# M050X.net
KiCad netlist of a schematic drawn in EAGLE
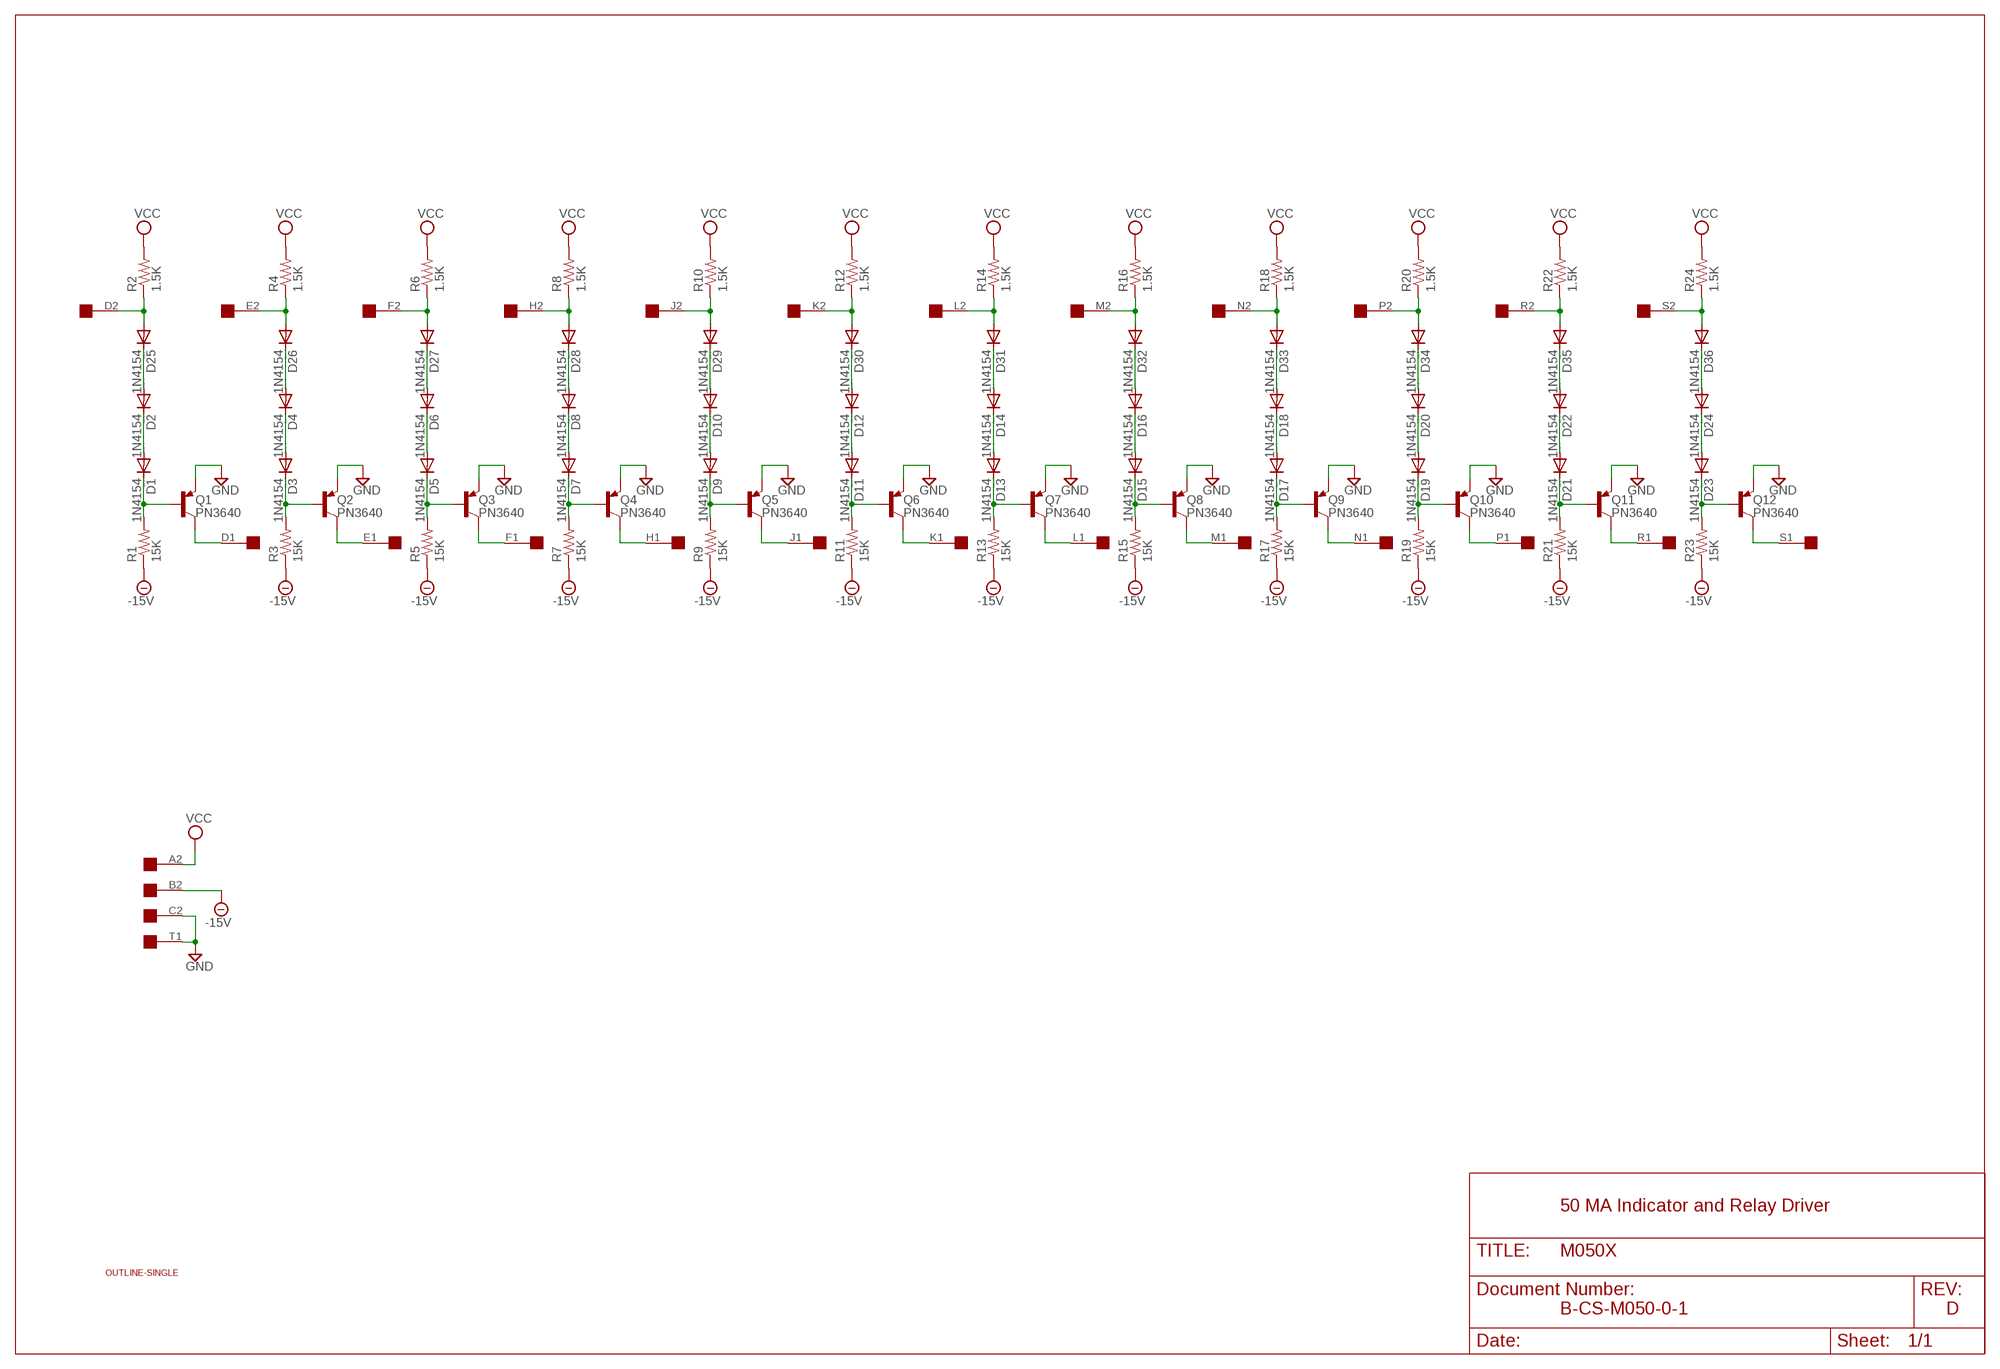
[diagram p0: schematic, sheet 1]

(export (version "E")
  (design (tool "Eeschema 10.0.6"))
  (components
    (comp (ref "D1")
      (value "1N4154")
      (footprint "eagle-import:DO35-10")
      (libsource (lib "eagle-import") (part "DIODE-DO35-10"))
    )
    (comp (ref "D2")
      (value "1N4154")
      (footprint "eagle-import:DO35-10")
      (libsource (lib "eagle-import") (part "DIODE-DO35-10"))
    )
    (comp (ref "D3")
      (value "1N4154")
      (footprint "eagle-import:DO35-10")
      (libsource (lib "eagle-import") (part "DIODE-DO35-10"))
    )
    (comp (ref "D4")
      (value "1N4154")
      (footprint "eagle-import:DO35-10")
      (libsource (lib "eagle-import") (part "DIODE-DO35-10"))
    )
    (comp (ref "D5")
      (value "1N4154")
      (footprint "eagle-import:DO35-10")
      (libsource (lib "eagle-import") (part "DIODE-DO35-10"))
    )
    (comp (ref "D6")
      (value "1N4154")
      (footprint "eagle-import:DO35-10")
      (libsource (lib "eagle-import") (part "DIODE-DO35-10"))
    )
    (comp (ref "D7")
      (value "1N4154")
      (footprint "eagle-import:DO35-10")
      (libsource (lib "eagle-import") (part "DIODE-DO35-10"))
    )
    (comp (ref "D8")
      (value "1N4154")
      (footprint "eagle-import:DO35-10")
      (libsource (lib "eagle-import") (part "DIODE-DO35-10"))
    )
    (comp (ref "D9")
      (value "1N4154")
      (footprint "eagle-import:DO35-10")
      (libsource (lib "eagle-import") (part "DIODE-DO35-10"))
    )
    (comp (ref "D10")
      (value "1N4154")
      (footprint "eagle-import:DO35-10")
      (libsource (lib "eagle-import") (part "DIODE-DO35-10"))
    )
    (comp (ref "D11")
      (value "1N4154")
      (footprint "eagle-import:DO35-10")
      (libsource (lib "eagle-import") (part "DIODE-DO35-10"))
    )
    (comp (ref "D12")
      (value "1N4154")
      (footprint "eagle-import:DO35-10")
      (libsource (lib "eagle-import") (part "DIODE-DO35-10"))
    )
    (comp (ref "D13")
      (value "1N4154")
      (footprint "eagle-import:DO35-10")
      (libsource (lib "eagle-import") (part "DIODE-DO35-10"))
    )
    (comp (ref "D14")
      (value "1N4154")
      (footprint "eagle-import:DO35-10")
      (libsource (lib "eagle-import") (part "DIODE-DO35-10"))
    )
    (comp (ref "D15")
      (value "1N4154")
      (footprint "eagle-import:DO35-10")
      (libsource (lib "eagle-import") (part "DIODE-DO35-10"))
    )
    (comp (ref "D16")
      (value "1N4154")
      (footprint "eagle-import:DO35-10")
      (libsource (lib "eagle-import") (part "DIODE-DO35-10"))
    )
    (comp (ref "D17")
      (value "1N4154")
      (footprint "eagle-import:DO35-10")
      (libsource (lib "eagle-import") (part "DIODE-DO35-10"))
    )
    (comp (ref "D18")
      (value "1N4154")
      (footprint "eagle-import:DO35-10")
      (libsource (lib "eagle-import") (part "DIODE-DO35-10"))
    )
    (comp (ref "D19")
      (value "1N4154")
      (footprint "eagle-import:DO35-10")
      (libsource (lib "eagle-import") (part "DIODE-DO35-10"))
    )
    (comp (ref "D20")
      (value "1N4154")
      (footprint "eagle-import:DO35-10")
      (libsource (lib "eagle-import") (part "DIODE-DO35-10"))
    )
    (comp (ref "D21")
      (value "1N4154")
      (footprint "eagle-import:DO35-10")
      (libsource (lib "eagle-import") (part "DIODE-DO35-10"))
    )
    (comp (ref "D22")
      (value "1N4154")
      (footprint "eagle-import:DO35-10")
      (libsource (lib "eagle-import") (part "DIODE-DO35-10"))
    )
    (comp (ref "D23")
      (value "1N4154")
      (footprint "eagle-import:DO35-10")
      (libsource (lib "eagle-import") (part "DIODE-DO35-10"))
    )
    (comp (ref "D24")
      (value "1N4154")
      (footprint "eagle-import:DO35-10")
      (libsource (lib "eagle-import") (part "DIODE-DO35-10"))
    )
    (comp (ref "D25")
      (value "1N4154")
      (footprint "eagle-import:DO35-10")
      (libsource (lib "eagle-import") (part "DIODE-DO35-10"))
    )
    (comp (ref "D26")
      (value "1N4154")
      (footprint "eagle-import:DO35-10")
      (libsource (lib "eagle-import") (part "DIODE-DO35-10"))
    )
    (comp (ref "D27")
      (value "1N4154")
      (footprint "eagle-import:DO35-10")
      (libsource (lib "eagle-import") (part "DIODE-DO35-10"))
    )
    (comp (ref "D28")
      (value "1N4154")
      (footprint "eagle-import:DO35-10")
      (libsource (lib "eagle-import") (part "DIODE-DO35-10"))
    )
    (comp (ref "D29")
      (value "1N4154")
      (footprint "eagle-import:DO35-10")
      (libsource (lib "eagle-import") (part "DIODE-DO35-10"))
    )
    (comp (ref "D30")
      (value "1N4154")
      (footprint "eagle-import:DO35-10")
      (libsource (lib "eagle-import") (part "DIODE-DO35-10"))
    )
    (comp (ref "D31")
      (value "1N4154")
      (footprint "eagle-import:DO35-10")
      (libsource (lib "eagle-import") (part "DIODE-DO35-10"))
    )
    (comp (ref "D32")
      (value "1N4154")
      (footprint "eagle-import:DO35-10")
      (libsource (lib "eagle-import") (part "DIODE-DO35-10"))
    )
    (comp (ref "D33")
      (value "1N4154")
      (footprint "eagle-import:DO35-10")
      (libsource (lib "eagle-import") (part "DIODE-DO35-10"))
    )
    (comp (ref "D34")
      (value "1N4154")
      (footprint "eagle-import:DO35-10")
      (libsource (lib "eagle-import") (part "DIODE-DO35-10"))
    )
    (comp (ref "D35")
      (value "1N4154")
      (footprint "eagle-import:DO35-10")
      (libsource (lib "eagle-import") (part "DIODE-DO35-10"))
    )
    (comp (ref "D36")
      (value "1N4154")
      (footprint "eagle-import:DO35-10")
      (libsource (lib "eagle-import") (part "DIODE-DO35-10"))
    )
    (comp (ref "Q1")
      (value "PN3640")
      (footprint "eagle-import:TO5")
      (libsource (lib "eagle-import") (part "-PNP-TO5"))
    )
    (comp (ref "Q2")
      (value "PN3640")
      (footprint "eagle-import:TO5")
      (libsource (lib "eagle-import") (part "-PNP-TO5"))
    )
    (comp (ref "Q3")
      (value "PN3640")
      (footprint "eagle-import:TO5")
      (libsource (lib "eagle-import") (part "-PNP-TO5"))
    )
    (comp (ref "Q4")
      (value "PN3640")
      (footprint "eagle-import:TO5")
      (libsource (lib "eagle-import") (part "-PNP-TO5"))
    )
    (comp (ref "Q5")
      (value "PN3640")
      (footprint "eagle-import:TO5")
      (libsource (lib "eagle-import") (part "-PNP-TO5"))
    )
    (comp (ref "Q6")
      (value "PN3640")
      (footprint "eagle-import:TO5")
      (libsource (lib "eagle-import") (part "-PNP-TO5"))
    )
    (comp (ref "Q7")
      (value "PN3640")
      (footprint "eagle-import:TO5")
      (libsource (lib "eagle-import") (part "-PNP-TO5"))
    )
    (comp (ref "Q8")
      (value "PN3640")
      (footprint "eagle-import:TO5")
      (libsource (lib "eagle-import") (part "-PNP-TO5"))
    )
    (comp (ref "Q9")
      (value "PN3640")
      (footprint "eagle-import:TO5")
      (libsource (lib "eagle-import") (part "-PNP-TO5"))
    )
    (comp (ref "Q10")
      (value "PN3640")
      (footprint "eagle-import:TO5")
      (libsource (lib "eagle-import") (part "-PNP-TO5"))
    )
    (comp (ref "Q11")
      (value "PN3640")
      (footprint "eagle-import:TO5")
      (libsource (lib "eagle-import") (part "-PNP-TO5"))
    )
    (comp (ref "Q12")
      (value "PN3640")
      (footprint "eagle-import:TO5")
      (libsource (lib "eagle-import") (part "-PNP-TO5"))
    )
    (comp (ref "R1")
      (value "15K")
      (footprint "eagle-import:0207_10")
      (libsource (lib "eagle-import") (part "R-US_0207/10"))
    )
    (comp (ref "R2")
      (value "1.5K")
      (footprint "eagle-import:0207_10")
      (libsource (lib "eagle-import") (part "R-US_0207/10"))
    )
    (comp (ref "R3")
      (value "15K")
      (footprint "eagle-import:0207_10")
      (libsource (lib "eagle-import") (part "R-US_0207/10"))
    )
    (comp (ref "R4")
      (value "1.5K")
      (footprint "eagle-import:0207_10")
      (libsource (lib "eagle-import") (part "R-US_0207/10"))
    )
    (comp (ref "R5")
      (value "15K")
      (footprint "eagle-import:0207_10")
      (libsource (lib "eagle-import") (part "R-US_0207/10"))
    )
    (comp (ref "R6")
      (value "1.5K")
      (footprint "eagle-import:0207_10")
      (libsource (lib "eagle-import") (part "R-US_0207/10"))
    )
    (comp (ref "R7")
      (value "15K")
      (footprint "eagle-import:0207_10")
      (libsource (lib "eagle-import") (part "R-US_0207/10"))
    )
    (comp (ref "R8")
      (value "1.5K")
      (footprint "eagle-import:0207_10")
      (libsource (lib "eagle-import") (part "R-US_0207/10"))
    )
    (comp (ref "R9")
      (value "15K")
      (footprint "eagle-import:0207_10")
      (libsource (lib "eagle-import") (part "R-US_0207/10"))
    )
    (comp (ref "R10")
      (value "1.5K")
      (footprint "eagle-import:0207_10")
      (libsource (lib "eagle-import") (part "R-US_0207/10"))
    )
    (comp (ref "R11")
      (value "15K")
      (footprint "eagle-import:0207_10")
      (libsource (lib "eagle-import") (part "R-US_0207/10"))
    )
    (comp (ref "R12")
      (value "1.5K")
      (footprint "eagle-import:0207_10")
      (libsource (lib "eagle-import") (part "R-US_0207/10"))
    )
    (comp (ref "R13")
      (value "15K")
      (footprint "eagle-import:0207_10")
      (libsource (lib "eagle-import") (part "R-US_0207/10"))
    )
    (comp (ref "R14")
      (value "1.5K")
      (footprint "eagle-import:0207_10")
      (libsource (lib "eagle-import") (part "R-US_0207/10"))
    )
    (comp (ref "R15")
      (value "15K")
      (footprint "eagle-import:0207_10")
      (libsource (lib "eagle-import") (part "R-US_0207/10"))
    )
    (comp (ref "R16")
      (value "1.5K")
      (footprint "eagle-import:0207_10")
      (libsource (lib "eagle-import") (part "R-US_0207/10"))
    )
    (comp (ref "R17")
      (value "15K")
      (footprint "eagle-import:0207_10")
      (libsource (lib "eagle-import") (part "R-US_0207/10"))
    )
    (comp (ref "R18")
      (value "1.5K")
      (footprint "eagle-import:0207_10")
      (libsource (lib "eagle-import") (part "R-US_0207/10"))
    )
    (comp (ref "R19")
      (value "15K")
      (footprint "eagle-import:0207_10")
      (libsource (lib "eagle-import") (part "R-US_0207/10"))
    )
    (comp (ref "R20")
      (value "1.5K")
      (footprint "eagle-import:0207_10")
      (libsource (lib "eagle-import") (part "R-US_0207/10"))
    )
    (comp (ref "R21")
      (value "15K")
      (footprint "eagle-import:0207_10")
      (libsource (lib "eagle-import") (part "R-US_0207/10"))
    )
    (comp (ref "R22")
      (value "1.5K")
      (footprint "eagle-import:0207_10")
      (libsource (lib "eagle-import") (part "R-US_0207/10"))
    )
    (comp (ref "R23")
      (value "15K")
      (footprint "eagle-import:0207_10")
      (libsource (lib "eagle-import") (part "R-US_0207/10"))
    )
    (comp (ref "R24")
      (value "1.5K")
      (footprint "eagle-import:0207_10")
      (libsource (lib "eagle-import") (part "R-US_0207/10"))
    )
    (comp (ref "U$1")
      (value "OUTLINE-SINGLE")
      (footprint "eagle-import:SINGLE")
      (libsource (lib "eagle-import") (part "OUTLINE-SINGLE"))
    )
    (comp (ref "U$2")
      (value "SINGLE")
      (footprint "eagle-import:EDGE-CON2")
      (libsource (lib "eagle-import") (part "SINGLE"))
    )
  )
  (nets
    (net (code "1") (name "-15V") (class "Default")
      (node (ref "R1") (pin "1") (pinfunction "1_1") (pintype "passive"))
      (node (ref "R11") (pin "1") (pinfunction "1_1") (pintype "passive"))
      (node (ref "R13") (pin "1") (pinfunction "1_1") (pintype "passive"))
      (node (ref "R15") (pin "1") (pinfunction "1_1") (pintype "passive"))
      (node (ref "R17") (pin "1") (pinfunction "1_1") (pintype "passive"))
      (node (ref "R19") (pin "1") (pinfunction "1_1") (pintype "passive"))
      (node (ref "R21") (pin "1") (pinfunction "1_1") (pintype "passive"))
      (node (ref "R23") (pin "1") (pinfunction "1_1") (pintype "passive"))
      (node (ref "R3") (pin "1") (pinfunction "1_1") (pintype "passive"))
      (node (ref "R5") (pin "1") (pinfunction "1_1") (pintype "passive"))
      (node (ref "R7") (pin "1") (pinfunction "1_1") (pintype "passive"))
      (node (ref "R9") (pin "1") (pinfunction "1_1") (pintype "passive"))
      (node (ref "U$2") (pin "B2") (pinfunction "1_B2") (pintype "bidirectional"))
    )
    (net (code "2") (name "GND") (class "Default")
      (node (ref "Q1") (pin "1") (pinfunction "E_1") (pintype "passive"))
      (node (ref "Q10") (pin "1") (pinfunction "E_1") (pintype "passive"))
      (node (ref "Q11") (pin "1") (pinfunction "E_1") (pintype "passive"))
      (node (ref "Q12") (pin "1") (pinfunction "E_1") (pintype "passive"))
      (node (ref "Q2") (pin "1") (pinfunction "E_1") (pintype "passive"))
      (node (ref "Q3") (pin "1") (pinfunction "E_1") (pintype "passive"))
      (node (ref "Q4") (pin "1") (pinfunction "E_1") (pintype "passive"))
      (node (ref "Q5") (pin "1") (pinfunction "E_1") (pintype "passive"))
      (node (ref "Q6") (pin "1") (pinfunction "E_1") (pintype "passive"))
      (node (ref "Q7") (pin "1") (pinfunction "E_1") (pintype "passive"))
      (node (ref "Q8") (pin "1") (pinfunction "E_1") (pintype "passive"))
      (node (ref "Q9") (pin "1") (pinfunction "E_1") (pintype "passive"))
      (node (ref "U$2") (pin "C2") (pinfunction "1_C2") (pintype "bidirectional"))
      (node (ref "U$2") (pin "T1") (pinfunction "1_T1") (pintype "bidirectional"))
    )
    (net (code "3") (name "Net-(D1-PadA)") (class "Default")
      (node (ref "D1") (pin "A") (pinfunction "A_A") (pintype "passive"))
      (node (ref "D2") (pin "C") (pinfunction "C_C") (pintype "passive"))
    )
    (net (code "4") (name "Net-(D2-PadA)") (class "Default")
      (node (ref "D2") (pin "A") (pinfunction "A_A") (pintype "passive"))
      (node (ref "D25") (pin "C") (pinfunction "C_C") (pintype "passive"))
    )
    (net (code "5") (name "Net-(D3-PadA)") (class "Default")
      (node (ref "D3") (pin "A") (pinfunction "A_A") (pintype "passive"))
      (node (ref "D4") (pin "C") (pinfunction "C_C") (pintype "passive"))
    )
    (net (code "6") (name "Net-(D5-PadA)") (class "Default")
      (node (ref "D5") (pin "A") (pinfunction "A_A") (pintype "passive"))
      (node (ref "D6") (pin "C") (pinfunction "C_C") (pintype "passive"))
    )
    (net (code "7") (name "Net-(D7-PadA)") (class "Default")
      (node (ref "D7") (pin "A") (pinfunction "A_A") (pintype "passive"))
      (node (ref "D8") (pin "C") (pinfunction "C_C") (pintype "passive"))
    )
    (net (code "8") (name "Net-(D10-PadA)") (class "Default")
      (node (ref "D10") (pin "A") (pinfunction "A_A") (pintype "passive"))
      (node (ref "D29") (pin "C") (pinfunction "C_C") (pintype "passive"))
    )
    (net (code "9") (name "Net-(D10-PadC)") (class "Default")
      (node (ref "D10") (pin "C") (pinfunction "C_C") (pintype "passive"))
      (node (ref "D9") (pin "A") (pinfunction "A_A") (pintype "passive"))
    )
    (net (code "10") (name "Net-(D11-PadA)") (class "Default")
      (node (ref "D11") (pin "A") (pinfunction "A_A") (pintype "passive"))
      (node (ref "D12") (pin "C") (pinfunction "C_C") (pintype "passive"))
    )
    (net (code "11") (name "Net-(D12-PadA)") (class "Default")
      (node (ref "D12") (pin "A") (pinfunction "A_A") (pintype "passive"))
      (node (ref "D30") (pin "C") (pinfunction "C_C") (pintype "passive"))
    )
    (net (code "12") (name "Net-(D13-PadA)") (class "Default")
      (node (ref "D13") (pin "A") (pinfunction "A_A") (pintype "passive"))
      (node (ref "D14") (pin "C") (pinfunction "C_C") (pintype "passive"))
    )
    (net (code "13") (name "Net-(D14-PadA)") (class "Default")
      (node (ref "D14") (pin "A") (pinfunction "A_A") (pintype "passive"))
      (node (ref "D31") (pin "C") (pinfunction "C_C") (pintype "passive"))
    )
    (net (code "14") (name "Net-(D15-PadA)") (class "Default")
      (node (ref "D15") (pin "A") (pinfunction "A_A") (pintype "passive"))
      (node (ref "D16") (pin "C") (pinfunction "C_C") (pintype "passive"))
    )
    (net (code "15") (name "Net-(D16-PadA)") (class "Default")
      (node (ref "D16") (pin "A") (pinfunction "A_A") (pintype "passive"))
      (node (ref "D32") (pin "C") (pinfunction "C_C") (pintype "passive"))
    )
    (net (code "16") (name "Net-(D17-PadA)") (class "Default")
      (node (ref "D17") (pin "A") (pinfunction "A_A") (pintype "passive"))
      (node (ref "D18") (pin "C") (pinfunction "C_C") (pintype "passive"))
    )
    (net (code "17") (name "Net-(D18-PadA)") (class "Default")
      (node (ref "D18") (pin "A") (pinfunction "A_A") (pintype "passive"))
      (node (ref "D33") (pin "C") (pinfunction "C_C") (pintype "passive"))
    )
    (net (code "18") (name "Net-(D19-PadA)") (class "Default")
      (node (ref "D19") (pin "A") (pinfunction "A_A") (pintype "passive"))
      (node (ref "D20") (pin "C") (pinfunction "C_C") (pintype "passive"))
    )
    (net (code "19") (name "Net-(D20-PadA)") (class "Default")
      (node (ref "D20") (pin "A") (pinfunction "A_A") (pintype "passive"))
      (node (ref "D34") (pin "C") (pinfunction "C_C") (pintype "passive"))
    )
    (net (code "20") (name "Net-(D21-PadA)") (class "Default")
      (node (ref "D21") (pin "A") (pinfunction "A_A") (pintype "passive"))
      (node (ref "D22") (pin "C") (pinfunction "C_C") (pintype "passive"))
    )
    (net (code "21") (name "Net-(D22-PadA)") (class "Default")
      (node (ref "D22") (pin "A") (pinfunction "A_A") (pintype "passive"))
      (node (ref "D35") (pin "C") (pinfunction "C_C") (pintype "passive"))
    )
    (net (code "22") (name "Net-(D23-PadA)") (class "Default")
      (node (ref "D23") (pin "A") (pinfunction "A_A") (pintype "passive"))
      (node (ref "D24") (pin "C") (pinfunction "C_C") (pintype "passive"))
    )
    (net (code "23") (name "Net-(D24-PadA)") (class "Default")
      (node (ref "D24") (pin "A") (pinfunction "A_A") (pintype "passive"))
      (node (ref "D36") (pin "C") (pinfunction "C_C") (pintype "passive"))
    )
    (net (code "24") (name "Net-(D26-PadC)") (class "Default")
      (node (ref "D26") (pin "C") (pinfunction "C_C") (pintype "passive"))
      (node (ref "D4") (pin "A") (pinfunction "A_A") (pintype "passive"))
    )
    (net (code "25") (name "Net-(D27-PadC)") (class "Default")
      (node (ref "D27") (pin "C") (pinfunction "C_C") (pintype "passive"))
      (node (ref "D6") (pin "A") (pinfunction "A_A") (pintype "passive"))
    )
    (net (code "26") (name "Net-(D28-PadC)") (class "Default")
      (node (ref "D28") (pin "C") (pinfunction "C_C") (pintype "passive"))
      (node (ref "D8") (pin "A") (pinfunction "A_A") (pintype "passive"))
    )
    (net (code "27") (name "Net-(Q1-B)") (class "Default")
      (node (ref "D1") (pin "C") (pinfunction "C_C") (pintype "passive"))
      (node (ref "Q1") (pin "2") (pinfunction "B_2") (pintype "passive"))
      (node (ref "R1") (pin "2") (pinfunction "2_2") (pintype "passive"))
    )
    (net (code "28") (name "Net-(Q1-C)") (class "Default")
      (node (ref "Q1") (pin "3") (pinfunction "C_3") (pintype "passive"))
      (node (ref "U$2") (pin "D1") (pinfunction "1_D1") (pintype "bidirectional"))
    )
    (net (code "29") (name "Net-(Q2-B)") (class "Default")
      (node (ref "D3") (pin "C") (pinfunction "C_C") (pintype "passive"))
      (node (ref "Q2") (pin "2") (pinfunction "B_2") (pintype "passive"))
      (node (ref "R3") (pin "2") (pinfunction "2_2") (pintype "passive"))
    )
    (net (code "30") (name "Net-(Q2-C)") (class "Default")
      (node (ref "Q2") (pin "3") (pinfunction "C_3") (pintype "passive"))
      (node (ref "U$2") (pin "E1") (pinfunction "1_E1") (pintype "bidirectional"))
    )
    (net (code "31") (name "Net-(Q3-B)") (class "Default")
      (node (ref "D5") (pin "C") (pinfunction "C_C") (pintype "passive"))
      (node (ref "Q3") (pin "2") (pinfunction "B_2") (pintype "passive"))
      (node (ref "R5") (pin "2") (pinfunction "2_2") (pintype "passive"))
    )
    (net (code "32") (name "Net-(Q3-C)") (class "Default")
      (node (ref "Q3") (pin "3") (pinfunction "C_3") (pintype "passive"))
      (node (ref "U$2") (pin "F1") (pinfunction "1_F1") (pintype "bidirectional"))
    )
    (net (code "33") (name "Net-(Q4-B)") (class "Default")
      (node (ref "D7") (pin "C") (pinfunction "C_C") (pintype "passive"))
      (node (ref "Q4") (pin "2") (pinfunction "B_2") (pintype "passive"))
      (node (ref "R7") (pin "2") (pinfunction "2_2") (pintype "passive"))
    )
    (net (code "34") (name "Net-(Q4-C)") (class "Default")
      (node (ref "Q4") (pin "3") (pinfunction "C_3") (pintype "passive"))
      (node (ref "U$2") (pin "H1") (pinfunction "1_H1") (pintype "bidirectional"))
    )
    (net (code "35") (name "Net-(Q5-B)") (class "Default")
      (node (ref "D9") (pin "C") (pinfunction "C_C") (pintype "passive"))
      (node (ref "Q5") (pin "2") (pinfunction "B_2") (pintype "passive"))
      (node (ref "R9") (pin "2") (pinfunction "2_2") (pintype "passive"))
    )
    (net (code "36") (name "Net-(Q5-C)") (class "Default")
      (node (ref "Q5") (pin "3") (pinfunction "C_3") (pintype "passive"))
      (node (ref "U$2") (pin "J1") (pinfunction "1_J1") (pintype "bidirectional"))
    )
    (net (code "37") (name "Net-(Q6-B)") (class "Default")
      (node (ref "D11") (pin "C") (pinfunction "C_C") (pintype "passive"))
      (node (ref "Q6") (pin "2") (pinfunction "B_2") (pintype "passive"))
      (node (ref "R11") (pin "2") (pinfunction "2_2") (pintype "passive"))
    )
    (net (code "38") (name "Net-(Q6-C)") (class "Default")
      (node (ref "Q6") (pin "3") (pinfunction "C_3") (pintype "passive"))
      (node (ref "U$2") (pin "K1") (pinfunction "1_K1") (pintype "bidirectional"))
    )
    (net (code "39") (name "Net-(Q7-B)") (class "Default")
      (node (ref "D13") (pin "C") (pinfunction "C_C") (pintype "passive"))
      (node (ref "Q7") (pin "2") (pinfunction "B_2") (pintype "passive"))
      (node (ref "R13") (pin "2") (pinfunction "2_2") (pintype "passive"))
    )
    (net (code "40") (name "Net-(Q7-C)") (class "Default")
      (node (ref "Q7") (pin "3") (pinfunction "C_3") (pintype "passive"))
      (node (ref "U$2") (pin "L1") (pinfunction "1_L1") (pintype "bidirectional"))
    )
    (net (code "41") (name "Net-(Q8-B)") (class "Default")
      (node (ref "D15") (pin "C") (pinfunction "C_C") (pintype "passive"))
      (node (ref "Q8") (pin "2") (pinfunction "B_2") (pintype "passive"))
      (node (ref "R15") (pin "2") (pinfunction "2_2") (pintype "passive"))
    )
    (net (code "42") (name "Net-(Q8-C)") (class "Default")
      (node (ref "Q8") (pin "3") (pinfunction "C_3") (pintype "passive"))
      (node (ref "U$2") (pin "M1") (pinfunction "1_M1") (pintype "bidirectional"))
    )
    (net (code "43") (name "Net-(Q9-B)") (class "Default")
      (node (ref "D17") (pin "C") (pinfunction "C_C") (pintype "passive"))
      (node (ref "Q9") (pin "2") (pinfunction "B_2") (pintype "passive"))
      (node (ref "R17") (pin "2") (pinfunction "2_2") (pintype "passive"))
    )
    (net (code "44") (name "Net-(Q9-C)") (class "Default")
      (node (ref "Q9") (pin "3") (pinfunction "C_3") (pintype "passive"))
      (node (ref "U$2") (pin "N1") (pinfunction "1_N1") (pintype "bidirectional"))
    )
    (net (code "45") (name "Net-(Q10-B)") (class "Default")
      (node (ref "D19") (pin "C") (pinfunction "C_C") (pintype "passive"))
      (node (ref "Q10") (pin "2") (pinfunction "B_2") (pintype "passive"))
      (node (ref "R19") (pin "2") (pinfunction "2_2") (pintype "passive"))
    )
    (net (code "46") (name "Net-(Q10-C)") (class "Default")
      (node (ref "Q10") (pin "3") (pinfunction "C_3") (pintype "passive"))
      (node (ref "U$2") (pin "P1") (pinfunction "1_P1") (pintype "bidirectional"))
    )
    (net (code "47") (name "Net-(Q11-B)") (class "Default")
      (node (ref "D21") (pin "C") (pinfunction "C_C") (pintype "passive"))
      (node (ref "Q11") (pin "2") (pinfunction "B_2") (pintype "passive"))
      (node (ref "R21") (pin "2") (pinfunction "2_2") (pintype "passive"))
    )
    (net (code "48") (name "Net-(Q11-C)") (class "Default")
      (node (ref "Q11") (pin "3") (pinfunction "C_3") (pintype "passive"))
      (node (ref "U$2") (pin "R1") (pinfunction "1_R1") (pintype "bidirectional"))
    )
    (net (code "49") (name "Net-(Q12-B)") (class "Default")
      (node (ref "D23") (pin "C") (pinfunction "C_C") (pintype "passive"))
      (node (ref "Q12") (pin "2") (pinfunction "B_2") (pintype "passive"))
      (node (ref "R23") (pin "2") (pinfunction "2_2") (pintype "passive"))
    )
    (net (code "50") (name "Net-(Q12-C)") (class "Default")
      (node (ref "Q12") (pin "3") (pinfunction "C_3") (pintype "passive"))
      (node (ref "U$2") (pin "S1") (pinfunction "1_S1") (pintype "bidirectional"))
    )
    (net (code "51") (name "Net-(U$2AB-1)") (class "Default")
      (node (ref "D35") (pin "A") (pinfunction "A_A") (pintype "passive"))
      (node (ref "R22") (pin "1") (pinfunction "1_1") (pintype "passive"))
      (node (ref "U$2") (pin "R2") (pinfunction "1_R2") (pintype "bidirectional"))
    )
    (net (code "52") (name "Net-(U$2AD-1)") (class "Default")
      (node (ref "D36") (pin "A") (pinfunction "A_A") (pintype "passive"))
      (node (ref "R24") (pin "1") (pinfunction "1_1") (pintype "passive"))
      (node (ref "U$2") (pin "S2") (pinfunction "1_S2") (pintype "bidirectional"))
    )
    (net (code "53") (name "Net-(U$2H-1)") (class "Default")
      (node (ref "D25") (pin "A") (pinfunction "A_A") (pintype "passive"))
      (node (ref "R2") (pin "1") (pinfunction "1_1") (pintype "passive"))
      (node (ref "U$2") (pin "D2") (pinfunction "1_D2") (pintype "bidirectional"))
    )
    (net (code "54") (name "Net-(U$2J-1)") (class "Default")
      (node (ref "D26") (pin "A") (pinfunction "A_A") (pintype "passive"))
      (node (ref "R4") (pin "1") (pinfunction "1_1") (pintype "passive"))
      (node (ref "U$2") (pin "E2") (pinfunction "1_E2") (pintype "bidirectional"))
    )
    (net (code "55") (name "Net-(U$2L-1)") (class "Default")
      (node (ref "D27") (pin "A") (pinfunction "A_A") (pintype "passive"))
      (node (ref "R6") (pin "1") (pinfunction "1_1") (pintype "passive"))
      (node (ref "U$2") (pin "F2") (pinfunction "1_F2") (pintype "bidirectional"))
    )
    (net (code "56") (name "Net-(U$2N-1)") (class "Default")
      (node (ref "D28") (pin "A") (pinfunction "A_A") (pintype "passive"))
      (node (ref "R8") (pin "1") (pinfunction "1_1") (pintype "passive"))
      (node (ref "U$2") (pin "H2") (pinfunction "1_H2") (pintype "bidirectional"))
    )
    (net (code "57") (name "Net-(U$2P-1)") (class "Default")
      (node (ref "D29") (pin "A") (pinfunction "A_A") (pintype "passive"))
      (node (ref "R10") (pin "1") (pinfunction "1_1") (pintype "passive"))
      (node (ref "U$2") (pin "J2") (pinfunction "1_J2") (pintype "bidirectional"))
    )
    (net (code "58") (name "Net-(U$2R-1)") (class "Default")
      (node (ref "D30") (pin "A") (pinfunction "A_A") (pintype "passive"))
      (node (ref "R12") (pin "1") (pinfunction "1_1") (pintype "passive"))
      (node (ref "U$2") (pin "K2") (pinfunction "1_K2") (pintype "bidirectional"))
    )
    (net (code "59") (name "Net-(U$2T-1)") (class "Default")
      (node (ref "D31") (pin "A") (pinfunction "A_A") (pintype "passive"))
      (node (ref "R14") (pin "1") (pinfunction "1_1") (pintype "passive"))
      (node (ref "U$2") (pin "L2") (pinfunction "1_L2") (pintype "bidirectional"))
    )
    (net (code "60") (name "Net-(U$2V-1)") (class "Default")
      (node (ref "D32") (pin "A") (pinfunction "A_A") (pintype "passive"))
      (node (ref "R16") (pin "1") (pinfunction "1_1") (pintype "passive"))
      (node (ref "U$2") (pin "M2") (pinfunction "1_M2") (pintype "bidirectional"))
    )
    (net (code "61") (name "Net-(U$2X-1)") (class "Default")
      (node (ref "D33") (pin "A") (pinfunction "A_A") (pintype "passive"))
      (node (ref "R18") (pin "1") (pinfunction "1_1") (pintype "passive"))
      (node (ref "U$2") (pin "N2") (pinfunction "1_N2") (pintype "bidirectional"))
    )
    (net (code "62") (name "Net-(U$2Z-1)") (class "Default")
      (node (ref "D34") (pin "A") (pinfunction "A_A") (pintype "passive"))
      (node (ref "R20") (pin "1") (pinfunction "1_1") (pintype "passive"))
      (node (ref "U$2") (pin "P2") (pinfunction "1_P2") (pintype "bidirectional"))
    )
    (net (code "63") (name "VCC") (class "Default")
      (node (ref "R10") (pin "2") (pinfunction "2_2") (pintype "passive"))
      (node (ref "R12") (pin "2") (pinfunction "2_2") (pintype "passive"))
      (node (ref "R14") (pin "2") (pinfunction "2_2") (pintype "passive"))
      (node (ref "R16") (pin "2") (pinfunction "2_2") (pintype "passive"))
      (node (ref "R18") (pin "2") (pinfunction "2_2") (pintype "passive"))
      (node (ref "R2") (pin "2") (pinfunction "2_2") (pintype "passive"))
      (node (ref "R20") (pin "2") (pinfunction "2_2") (pintype "passive"))
      (node (ref "R22") (pin "2") (pinfunction "2_2") (pintype "passive"))
      (node (ref "R24") (pin "2") (pinfunction "2_2") (pintype "passive"))
      (node (ref "R4") (pin "2") (pinfunction "2_2") (pintype "passive"))
      (node (ref "R6") (pin "2") (pinfunction "2_2") (pintype "passive"))
      (node (ref "R8") (pin "2") (pinfunction "2_2") (pintype "passive"))
      (node (ref "U$2") (pin "A2") (pinfunction "1_A2") (pintype "bidirectional"))
    )
  )
)
